# WriteROM_32K_Proto.net
KiCad netlist of a schematic drawn in EAGLE
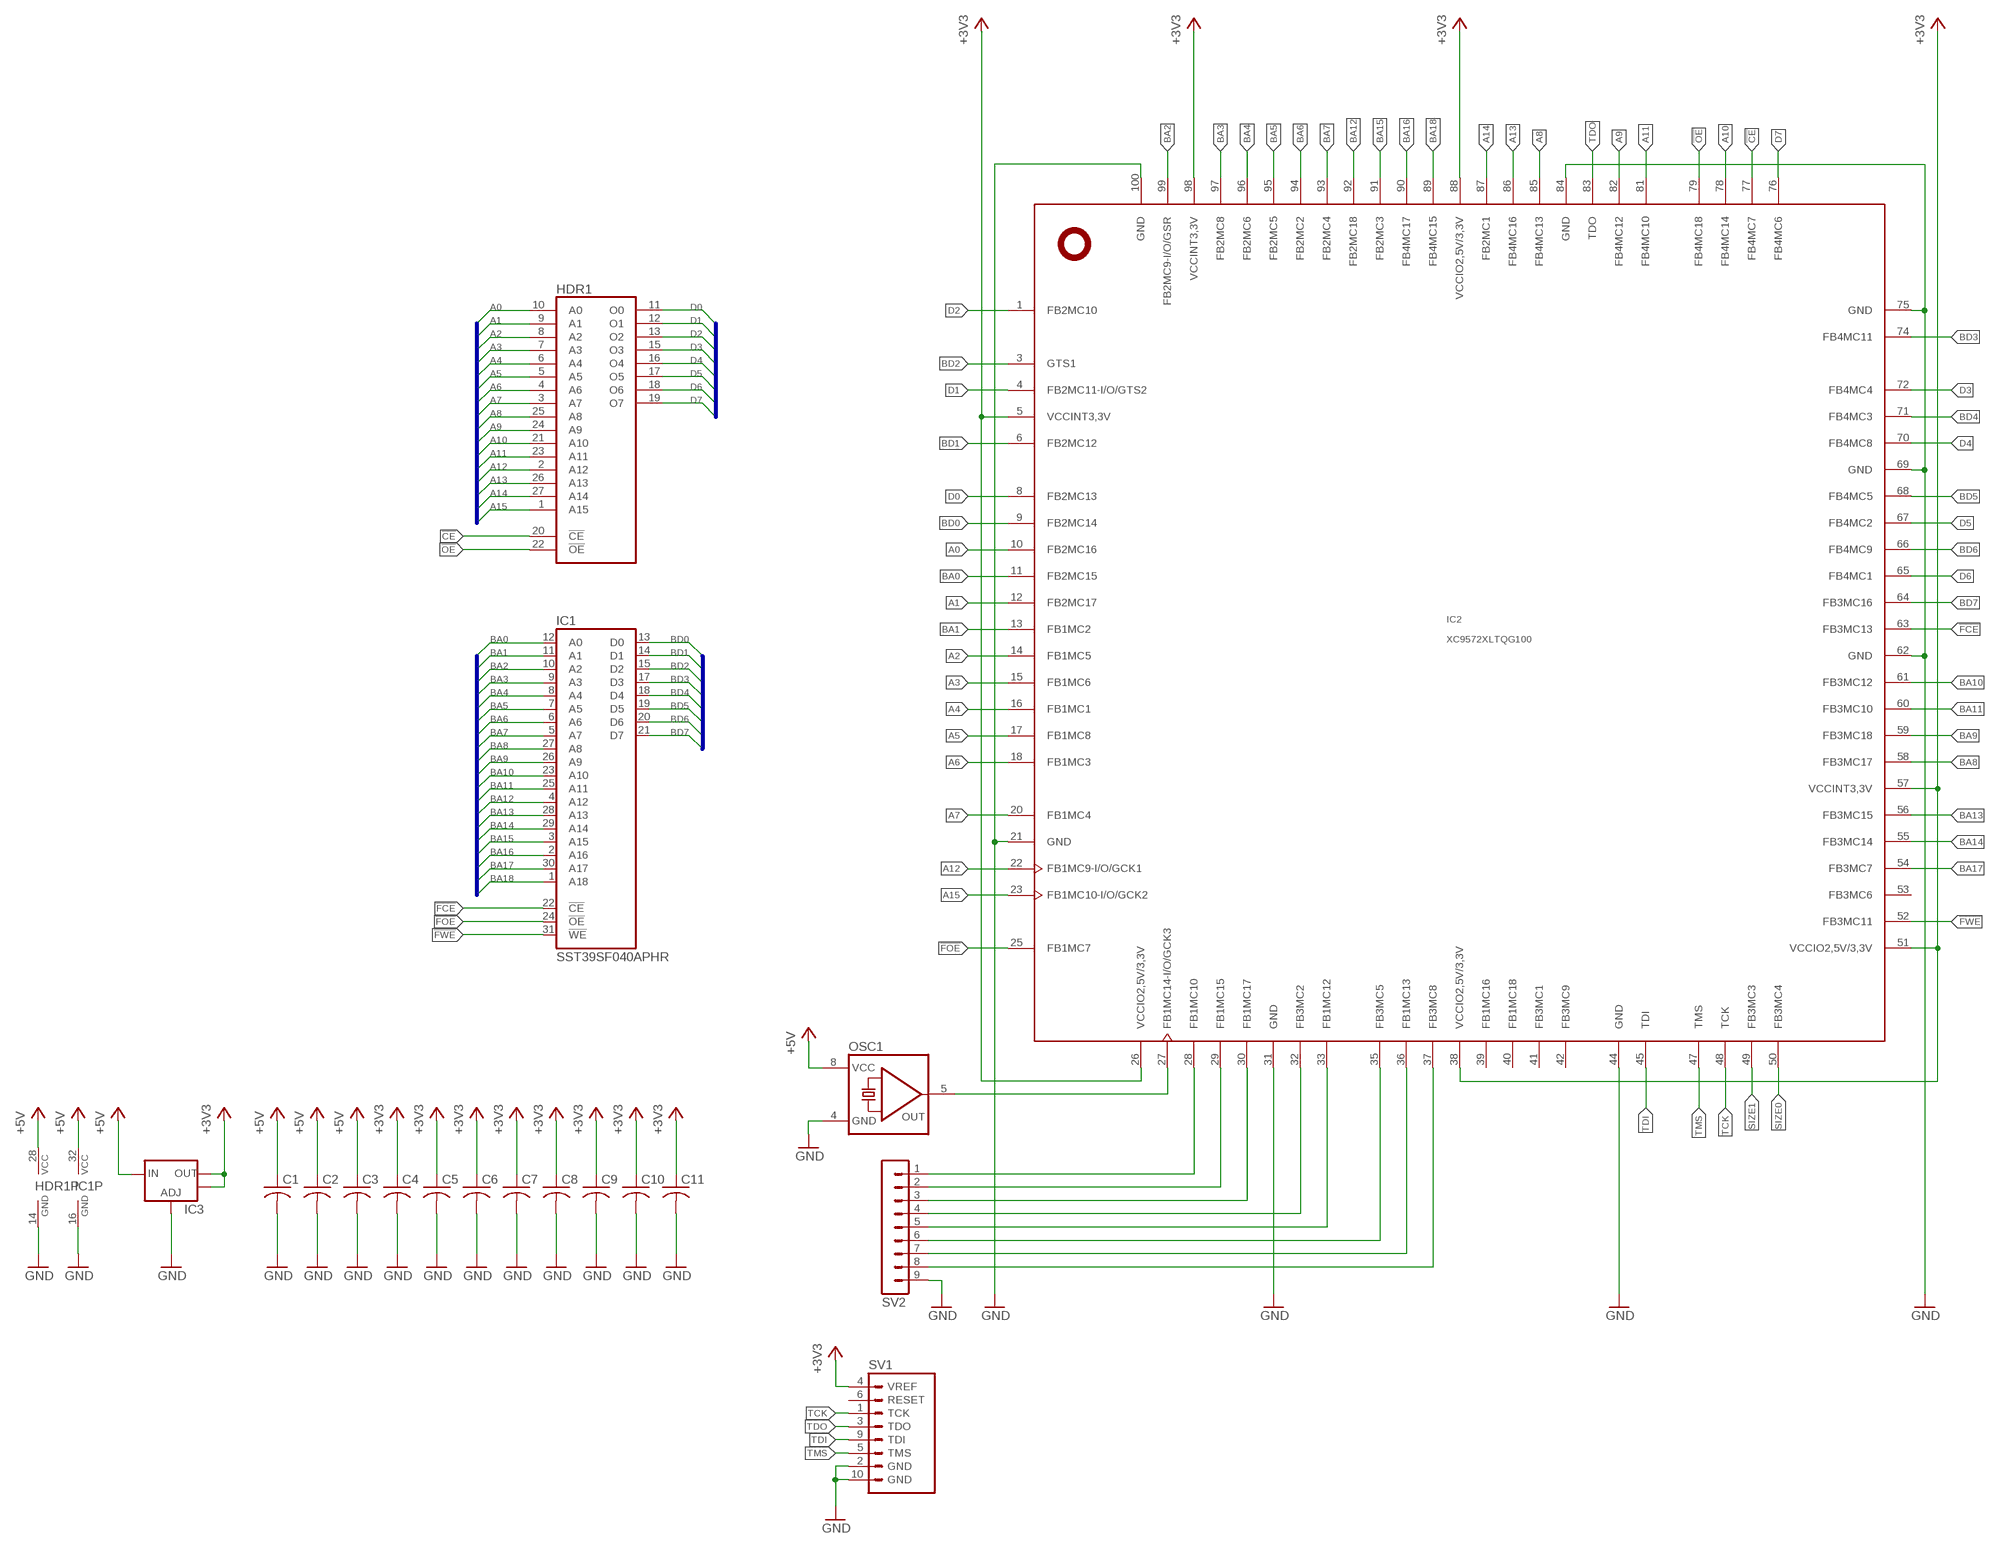
[diagram p0: schematic, sheet 1]

(export (version "E")
  (design (tool "Eeschema 10.0.6"))
  (components
    (comp (ref "C1")
      (value "C-USC0805")
      (footprint "eagle-import:C0805")
      (libsource (lib "eagle-import") (part "C-USC0805"))
    )
    (comp (ref "C2")
      (value "C-USC0402")
      (footprint "eagle-import:C0402")
      (libsource (lib "eagle-import") (part "C-USC0402"))
    )
    (comp (ref "C3")
      (value "C-USC0402")
      (footprint "eagle-import:C0402")
      (libsource (lib "eagle-import") (part "C-USC0402"))
    )
    (comp (ref "C4")
      (value "C-USC0805")
      (footprint "eagle-import:C0805")
      (libsource (lib "eagle-import") (part "C-USC0805"))
    )
    (comp (ref "C5")
      (value "C-USC0402")
      (footprint "eagle-import:C0402")
      (libsource (lib "eagle-import") (part "C-USC0402"))
    )
    (comp (ref "C6")
      (value "C-USC0402")
      (footprint "eagle-import:C0402")
      (libsource (lib "eagle-import") (part "C-USC0402"))
    )
    (comp (ref "C7")
      (value "C-USC0402")
      (footprint "eagle-import:C0402")
      (libsource (lib "eagle-import") (part "C-USC0402"))
    )
    (comp (ref "C8")
      (value "C-USC0402")
      (footprint "eagle-import:C0402")
      (libsource (lib "eagle-import") (part "C-USC0402"))
    )
    (comp (ref "C9")
      (value "C-USC0402")
      (footprint "eagle-import:C0402")
      (libsource (lib "eagle-import") (part "C-USC0402"))
    )
    (comp (ref "C10")
      (value "C-USC0402")
      (footprint "eagle-import:C0402")
      (libsource (lib "eagle-import") (part "C-USC0402"))
    )
    (comp (ref "C11")
      (value "C-USC0402")
      (footprint "eagle-import:C0402")
      (libsource (lib "eagle-import") (part "C-USC0402"))
    )
    (comp (ref "HDR1")
      (value "27512")
      (footprint "eagle-import:DIL28")
      (libsource (lib "eagle-import") (part "27512"))
    )
    (comp (ref "IC1")
      (value "SST39SF040APHR")
      (footprint "eagle-import:DIL32-RP")
      (libsource (lib "eagle-import") (part "SST39SF040APHR"))
    )
    (comp (ref "IC2")
      (value "XC9572XLTQG100")
      (footprint "eagle-import:TQFP100")
      (libsource (lib "eagle-import") (part "XC9572XLTQG100"))
    )
    (comp (ref "IC3")
      (value "V_REG_LM1117SOT223")
      (footprint "eagle-import:SOT223")
      (libsource (lib "eagle-import") (part "V_REG_LM1117SOT223"))
    )
    (comp (ref "OSC1")
      (value "QG5460")
      (footprint "eagle-import:DIL08S")
      (libsource (lib "eagle-import") (part "QG5460"))
    )
    (comp (ref "SV1")
      (value "JTAG")
      (footprint "eagle-import:JTAG")
      (libsource (lib "eagle-import") (part "JTAG"))
    )
    (comp (ref "SV2")
      (value "MA09-1")
      (footprint "eagle-import:MA09-1")
      (libsource (lib "eagle-import") (part "MA09-1"))
    )
  )
  (nets
    (net (code "1") (name "+3V3") (class "Default")
      (node (ref "C10") (pin "1") (pinfunction "1_1") (pintype "passive"))
      (node (ref "C11") (pin "1") (pinfunction "1_1") (pintype "passive"))
      (node (ref "C4") (pin "1") (pinfunction "1_1") (pintype "passive"))
      (node (ref "C5") (pin "1") (pinfunction "1_1") (pintype "passive"))
      (node (ref "C6") (pin "1") (pinfunction "1_1") (pintype "passive"))
      (node (ref "C7") (pin "1") (pinfunction "1_1") (pintype "passive"))
      (node (ref "C8") (pin "1") (pinfunction "1_1") (pintype "passive"))
      (node (ref "C9") (pin "1") (pinfunction "1_1") (pintype "passive"))
      (node (ref "IC2") (pin "26") (pinfunction "VCCIO2,5V/3,3V_26") (pintype "power_in"))
      (node (ref "IC2") (pin "38") (pinfunction "VCCIO2,5V/3,3V_38") (pintype "power_in"))
      (node (ref "IC2") (pin "5") (pinfunction "VCCINT3,3V_5") (pintype "power_in"))
      (node (ref "IC2") (pin "51") (pinfunction "VCCIO2,5V/3,3V_51") (pintype "power_in"))
      (node (ref "IC2") (pin "57") (pinfunction "VCCINT3,3V_57") (pintype "power_in"))
      (node (ref "IC2") (pin "88") (pinfunction "VCCIO2,5V/3,3V_88") (pintype "power_in"))
      (node (ref "IC2") (pin "98") (pinfunction "VCCINT3,3V_98") (pintype "power_in"))
      (node (ref "IC3") (pin "2") (pinfunction "OUT_2") (pintype "output"))
      (node (ref "IC3") (pin "4") (pinfunction "OUT_4") (pintype "output"))
      (node (ref "SV1") (pin "4") (pinfunction "VREF_4") (pintype "power_in"))
    )
    (net (code "2") (name "+5V") (class "Default")
      (node (ref "C1") (pin "1") (pinfunction "1_1") (pintype "passive"))
      (node (ref "C2") (pin "1") (pinfunction "1_1") (pintype "passive"))
      (node (ref "C3") (pin "1") (pinfunction "1_1") (pintype "passive"))
      (node (ref "HDR1") (pin "28") (pinfunction "VCC_28") (pintype "power_in"))
      (node (ref "IC1") (pin "32") (pinfunction "VCC_32") (pintype "power_in"))
      (node (ref "IC3") (pin "3") (pinfunction "IN_3") (pintype "input"))
      (node (ref "OSC1") (pin "8") (pinfunction "VCC_8") (pintype "power_in"))
    )
    (net (code "3") (name "/~{CE}") (class "Default")
      (node (ref "HDR1") (pin "20") (pinfunction "~{CE}_20") (pintype "input"))
      (node (ref "IC2") (pin "77") (pinfunction "FB4MC7_77") (pintype "bidirectional"))
    )
    (net (code "4") (name "/~{FCE}") (class "Default")
      (node (ref "IC1") (pin "22") (pinfunction "~{CE}_22") (pintype "input"))
      (node (ref "IC2") (pin "63") (pinfunction "FB3MC13_63") (pintype "bidirectional"))
    )
    (net (code "5") (name "/~{FOE}") (class "Default")
      (node (ref "IC1") (pin "24") (pinfunction "~{OE}_24") (pintype "input"))
      (node (ref "IC2") (pin "25") (pinfunction "FB1MC7_25") (pintype "bidirectional"))
    )
    (net (code "6") (name "/~{FWE}") (class "Default")
      (node (ref "IC1") (pin "31") (pinfunction "~{WE}_31") (pintype "input"))
      (node (ref "IC2") (pin "52") (pinfunction "FB3MC11_52") (pintype "bidirectional"))
    )
    (net (code "7") (name "/~{OE}") (class "Default")
      (node (ref "HDR1") (pin "22") (pinfunction "~{OE}_22") (pintype "input"))
      (node (ref "IC2") (pin "79") (pinfunction "FB4MC18_79") (pintype "bidirectional"))
    )
    (net (code "8") (name "A0") (class "Default")
      (node (ref "HDR1") (pin "10") (pinfunction "A0_10") (pintype "input"))
      (node (ref "IC2") (pin "10") (pinfunction "FB2MC16_10") (pintype "bidirectional"))
    )
    (net (code "9") (name "A1") (class "Default")
      (node (ref "HDR1") (pin "9") (pinfunction "A1_9") (pintype "input"))
      (node (ref "IC2") (pin "12") (pinfunction "FB2MC17_12") (pintype "bidirectional"))
    )
    (net (code "10") (name "A2") (class "Default")
      (node (ref "HDR1") (pin "8") (pinfunction "A2_8") (pintype "input"))
      (node (ref "IC2") (pin "14") (pinfunction "FB1MC5_14") (pintype "bidirectional"))
    )
    (net (code "11") (name "A3") (class "Default")
      (node (ref "HDR1") (pin "7") (pinfunction "A3_7") (pintype "input"))
      (node (ref "IC2") (pin "15") (pinfunction "FB1MC6_15") (pintype "bidirectional"))
    )
    (net (code "12") (name "A4") (class "Default")
      (node (ref "HDR1") (pin "6") (pinfunction "A4_6") (pintype "input"))
      (node (ref "IC2") (pin "16") (pinfunction "FB1MC1_16") (pintype "bidirectional"))
    )
    (net (code "13") (name "A5") (class "Default")
      (node (ref "HDR1") (pin "5") (pinfunction "A5_5") (pintype "input"))
      (node (ref "IC2") (pin "17") (pinfunction "FB1MC8_17") (pintype "bidirectional"))
    )
    (net (code "14") (name "A6") (class "Default")
      (node (ref "HDR1") (pin "4") (pinfunction "A6_4") (pintype "input"))
      (node (ref "IC2") (pin "18") (pinfunction "FB1MC3_18") (pintype "bidirectional"))
    )
    (net (code "15") (name "A7") (class "Default")
      (node (ref "HDR1") (pin "3") (pinfunction "A7_3") (pintype "input"))
      (node (ref "IC2") (pin "20") (pinfunction "FB1MC4_20") (pintype "bidirectional"))
    )
    (net (code "16") (name "A8") (class "Default")
      (node (ref "HDR1") (pin "25") (pinfunction "A8_25") (pintype "input"))
      (node (ref "IC2") (pin "85") (pinfunction "FB4MC13_85") (pintype "bidirectional"))
    )
    (net (code "17") (name "A9") (class "Default")
      (node (ref "HDR1") (pin "24") (pinfunction "A9_24") (pintype "input"))
      (node (ref "IC2") (pin "82") (pinfunction "FB4MC12_82") (pintype "bidirectional"))
    )
    (net (code "18") (name "A10") (class "Default")
      (node (ref "HDR1") (pin "21") (pinfunction "A10_21") (pintype "input"))
      (node (ref "IC2") (pin "78") (pinfunction "FB4MC14_78") (pintype "bidirectional"))
    )
    (net (code "19") (name "A11") (class "Default")
      (node (ref "HDR1") (pin "23") (pinfunction "A11_23") (pintype "input"))
      (node (ref "IC2") (pin "81") (pinfunction "FB4MC10_81") (pintype "bidirectional"))
    )
    (net (code "20") (name "A12") (class "Default")
      (node (ref "HDR1") (pin "2") (pinfunction "A12_2") (pintype "input"))
      (node (ref "IC2") (pin "22") (pinfunction "FB1MC9-I/O/GCK1_22") (pintype "bidirectional"))
    )
    (net (code "21") (name "A13") (class "Default")
      (node (ref "HDR1") (pin "26") (pinfunction "A13_26") (pintype "input"))
      (node (ref "IC2") (pin "86") (pinfunction "FB4MC16_86") (pintype "bidirectional"))
    )
    (net (code "22") (name "A14") (class "Default")
      (node (ref "HDR1") (pin "27") (pinfunction "A14_27") (pintype "input"))
      (node (ref "IC2") (pin "87") (pinfunction "FB2MC1_87") (pintype "bidirectional"))
    )
    (net (code "23") (name "A15") (class "Default")
      (node (ref "HDR1") (pin "1") (pinfunction "A15_1") (pintype "input"))
      (node (ref "IC2") (pin "23") (pinfunction "FB1MC10-I/O/GCK2_23") (pintype "bidirectional"))
    )
    (net (code "24") (name "BA0") (class "Default")
      (node (ref "IC1") (pin "12") (pinfunction "A0_12") (pintype "input"))
      (node (ref "IC2") (pin "11") (pinfunction "FB2MC15_11") (pintype "bidirectional"))
    )
    (net (code "25") (name "BA1") (class "Default")
      (node (ref "IC1") (pin "11") (pinfunction "A1_11") (pintype "input"))
      (node (ref "IC2") (pin "13") (pinfunction "FB1MC2_13") (pintype "bidirectional"))
    )
    (net (code "26") (name "BA2") (class "Default")
      (node (ref "IC1") (pin "10") (pinfunction "A2_10") (pintype "input"))
      (node (ref "IC2") (pin "99") (pinfunction "FB2MC9-I/O/GSR_99") (pintype "bidirectional"))
    )
    (net (code "27") (name "BA3") (class "Default")
      (node (ref "IC1") (pin "9") (pinfunction "A3_9") (pintype "input"))
      (node (ref "IC2") (pin "97") (pinfunction "FB2MC8_97") (pintype "bidirectional"))
    )
    (net (code "28") (name "BA4") (class "Default")
      (node (ref "IC1") (pin "8") (pinfunction "A4_8") (pintype "input"))
      (node (ref "IC2") (pin "96") (pinfunction "FB2MC6_96") (pintype "bidirectional"))
    )
    (net (code "29") (name "BA5") (class "Default")
      (node (ref "IC1") (pin "7") (pinfunction "A5_7") (pintype "input"))
      (node (ref "IC2") (pin "95") (pinfunction "FB2MC5_95") (pintype "bidirectional"))
    )
    (net (code "30") (name "BA6") (class "Default")
      (node (ref "IC1") (pin "6") (pinfunction "A6_6") (pintype "input"))
      (node (ref "IC2") (pin "94") (pinfunction "FB2MC2_94") (pintype "bidirectional"))
    )
    (net (code "31") (name "BA7") (class "Default")
      (node (ref "IC1") (pin "5") (pinfunction "A7_5") (pintype "input"))
      (node (ref "IC2") (pin "93") (pinfunction "FB2MC4_93") (pintype "bidirectional"))
    )
    (net (code "32") (name "BA8") (class "Default")
      (node (ref "IC1") (pin "27") (pinfunction "A8_27") (pintype "input"))
      (node (ref "IC2") (pin "58") (pinfunction "FB3MC17_58") (pintype "bidirectional"))
    )
    (net (code "33") (name "BA9") (class "Default")
      (node (ref "IC1") (pin "26") (pinfunction "A9_26") (pintype "input"))
      (node (ref "IC2") (pin "59") (pinfunction "FB3MC18_59") (pintype "bidirectional"))
    )
    (net (code "34") (name "BA10") (class "Default")
      (node (ref "IC1") (pin "23") (pinfunction "A10_23") (pintype "input"))
      (node (ref "IC2") (pin "61") (pinfunction "FB3MC12_61") (pintype "bidirectional"))
    )
    (net (code "35") (name "BA11") (class "Default")
      (node (ref "IC1") (pin "25") (pinfunction "A11_25") (pintype "input"))
      (node (ref "IC2") (pin "60") (pinfunction "FB3MC10_60") (pintype "bidirectional"))
    )
    (net (code "36") (name "BA12") (class "Default")
      (node (ref "IC1") (pin "4") (pinfunction "A12_4") (pintype "input"))
      (node (ref "IC2") (pin "92") (pinfunction "FB2MC18_92") (pintype "bidirectional"))
    )
    (net (code "37") (name "BA13") (class "Default")
      (node (ref "IC1") (pin "28") (pinfunction "A13_28") (pintype "input"))
      (node (ref "IC2") (pin "56") (pinfunction "FB3MC15_56") (pintype "bidirectional"))
    )
    (net (code "38") (name "BA14") (class "Default")
      (node (ref "IC1") (pin "29") (pinfunction "A14_29") (pintype "input"))
      (node (ref "IC2") (pin "55") (pinfunction "FB3MC14_55") (pintype "bidirectional"))
    )
    (net (code "39") (name "BA15") (class "Default")
      (node (ref "IC1") (pin "3") (pinfunction "A15_3") (pintype "input"))
      (node (ref "IC2") (pin "91") (pinfunction "FB2MC3_91") (pintype "bidirectional"))
    )
    (net (code "40") (name "BA16") (class "Default")
      (node (ref "IC1") (pin "2") (pinfunction "A16_2") (pintype "input"))
      (node (ref "IC2") (pin "90") (pinfunction "FB4MC17_90") (pintype "bidirectional"))
    )
    (net (code "41") (name "BA17") (class "Default")
      (node (ref "IC1") (pin "30") (pinfunction "A17_30") (pintype "input"))
      (node (ref "IC2") (pin "54") (pinfunction "FB3MC7_54") (pintype "bidirectional"))
    )
    (net (code "42") (name "BA18") (class "Default")
      (node (ref "IC1") (pin "1") (pinfunction "A18_1") (pintype "input"))
      (node (ref "IC2") (pin "89") (pinfunction "FB4MC15_89") (pintype "bidirectional"))
    )
    (net (code "43") (name "BD0") (class "Default")
      (node (ref "IC1") (pin "13") (pinfunction "D0_13") (pintype "bidirectional"))
      (node (ref "IC2") (pin "9") (pinfunction "FB2MC14_9") (pintype "bidirectional"))
    )
    (net (code "44") (name "BD1") (class "Default")
      (node (ref "IC1") (pin "14") (pinfunction "D1_14") (pintype "bidirectional"))
      (node (ref "IC2") (pin "6") (pinfunction "FB2MC12_6") (pintype "bidirectional"))
    )
    (net (code "45") (name "BD2") (class "Default")
      (node (ref "IC1") (pin "15") (pinfunction "D2_15") (pintype "bidirectional"))
      (node (ref "IC2") (pin "3") (pinfunction "GTS1_3") (pintype "bidirectional"))
    )
    (net (code "46") (name "BD3") (class "Default")
      (node (ref "IC1") (pin "17") (pinfunction "D3_17") (pintype "bidirectional"))
      (node (ref "IC2") (pin "74") (pinfunction "FB4MC11_74") (pintype "bidirectional"))
    )
    (net (code "47") (name "BD4") (class "Default")
      (node (ref "IC1") (pin "18") (pinfunction "D4_18") (pintype "bidirectional"))
      (node (ref "IC2") (pin "71") (pinfunction "FB4MC3_71") (pintype "bidirectional"))
    )
    (net (code "48") (name "BD5") (class "Default")
      (node (ref "IC1") (pin "19") (pinfunction "D5_19") (pintype "bidirectional"))
      (node (ref "IC2") (pin "68") (pinfunction "FB4MC5_68") (pintype "bidirectional"))
    )
    (net (code "49") (name "BD6") (class "Default")
      (node (ref "IC1") (pin "20") (pinfunction "D6_20") (pintype "bidirectional"))
      (node (ref "IC2") (pin "66") (pinfunction "FB4MC9_66") (pintype "bidirectional"))
    )
    (net (code "50") (name "BD7") (class "Default")
      (node (ref "IC1") (pin "21") (pinfunction "D7_21") (pintype "bidirectional"))
      (node (ref "IC2") (pin "64") (pinfunction "FB3MC16_64") (pintype "bidirectional"))
    )
    (net (code "51") (name "D0") (class "Default")
      (node (ref "HDR1") (pin "11") (pinfunction "O0_11") (pintype "tri_state"))
      (node (ref "IC2") (pin "8") (pinfunction "FB2MC13_8") (pintype "bidirectional"))
    )
    (net (code "52") (name "D1") (class "Default")
      (node (ref "HDR1") (pin "12") (pinfunction "O1_12") (pintype "tri_state"))
      (node (ref "IC2") (pin "4") (pinfunction "FB2MC11-I/O/GTS2_4") (pintype "bidirectional"))
    )
    (net (code "53") (name "D2") (class "Default")
      (node (ref "HDR1") (pin "13") (pinfunction "O2_13") (pintype "tri_state"))
      (node (ref "IC2") (pin "1") (pinfunction "FB2MC10_1") (pintype "bidirectional"))
    )
    (net (code "54") (name "D3") (class "Default")
      (node (ref "HDR1") (pin "15") (pinfunction "O3_15") (pintype "tri_state"))
      (node (ref "IC2") (pin "72") (pinfunction "FB4MC4_72") (pintype "bidirectional"))
    )
    (net (code "55") (name "D4") (class "Default")
      (node (ref "HDR1") (pin "16") (pinfunction "O4_16") (pintype "tri_state"))
      (node (ref "IC2") (pin "70") (pinfunction "FB4MC8_70") (pintype "bidirectional"))
    )
    (net (code "56") (name "D5") (class "Default")
      (node (ref "HDR1") (pin "17") (pinfunction "O5_17") (pintype "tri_state"))
      (node (ref "IC2") (pin "67") (pinfunction "FB4MC2_67") (pintype "bidirectional"))
    )
    (net (code "57") (name "D6") (class "Default")
      (node (ref "HDR1") (pin "18") (pinfunction "O6_18") (pintype "tri_state"))
      (node (ref "IC2") (pin "65") (pinfunction "FB4MC1_65") (pintype "bidirectional"))
    )
    (net (code "58") (name "D7") (class "Default")
      (node (ref "HDR1") (pin "19") (pinfunction "O7_19") (pintype "tri_state"))
      (node (ref "IC2") (pin "76") (pinfunction "FB4MC6_76") (pintype "bidirectional"))
    )
    (net (code "59") (name "GND") (class "Default")
      (node (ref "C1") (pin "2") (pinfunction "2_2") (pintype "passive"))
      (node (ref "C10") (pin "2") (pinfunction "2_2") (pintype "passive"))
      (node (ref "C11") (pin "2") (pinfunction "2_2") (pintype "passive"))
      (node (ref "C2") (pin "2") (pinfunction "2_2") (pintype "passive"))
      (node (ref "C3") (pin "2") (pinfunction "2_2") (pintype "passive"))
      (node (ref "C4") (pin "2") (pinfunction "2_2") (pintype "passive"))
      (node (ref "C5") (pin "2") (pinfunction "2_2") (pintype "passive"))
      (node (ref "C6") (pin "2") (pinfunction "2_2") (pintype "passive"))
      (node (ref "C7") (pin "2") (pinfunction "2_2") (pintype "passive"))
      (node (ref "C8") (pin "2") (pinfunction "2_2") (pintype "passive"))
      (node (ref "C9") (pin "2") (pinfunction "2_2") (pintype "passive"))
      (node (ref "HDR1") (pin "14") (pinfunction "GND_14") (pintype "power_in"))
      (node (ref "IC1") (pin "16") (pinfunction "GND_16") (pintype "power_in"))
      (node (ref "IC2") (pin "100") (pinfunction "GND_100") (pintype "power_in"))
      (node (ref "IC2") (pin "21") (pinfunction "GND_21") (pintype "power_in"))
      (node (ref "IC2") (pin "31") (pinfunction "GND_31") (pintype "power_in"))
      (node (ref "IC2") (pin "44") (pinfunction "GND_44") (pintype "power_in"))
      (node (ref "IC2") (pin "62") (pinfunction "GND_62") (pintype "power_in"))
      (node (ref "IC2") (pin "69") (pinfunction "GND_69") (pintype "power_in"))
      (node (ref "IC2") (pin "75") (pinfunction "GND_75") (pintype "power_in"))
      (node (ref "IC2") (pin "84") (pinfunction "GND_84") (pintype "power_in"))
      (node (ref "IC3") (pin "1") (pinfunction "ADJ_1") (pintype "input"))
      (node (ref "OSC1") (pin "4") (pinfunction "GND_4") (pintype "power_in"))
      (node (ref "SV1") (pin "10") (pinfunction "GND_10") (pintype "power_in"))
      (node (ref "SV1") (pin "2") (pinfunction "GND_2") (pintype "power_in"))
      (node (ref "SV2") (pin "9") (pinfunction "9_9") (pintype "passive"))
    )
    (net (code "60") (name "Net-(IC2-FB1MC10)") (class "Default")
      (node (ref "IC2") (pin "28") (pinfunction "FB1MC10_28") (pintype "bidirectional"))
      (node (ref "SV2") (pin "1") (pinfunction "1_1") (pintype "passive"))
    )
    (net (code "61") (name "Net-(IC2-FB1MC12)") (class "Default")
      (node (ref "IC2") (pin "33") (pinfunction "FB1MC12_33") (pintype "bidirectional"))
      (node (ref "SV2") (pin "5") (pinfunction "5_5") (pintype "passive"))
    )
    (net (code "62") (name "Net-(IC2-FB1MC13)") (class "Default")
      (node (ref "IC2") (pin "36") (pinfunction "FB1MC13_36") (pintype "bidirectional"))
      (node (ref "SV2") (pin "7") (pinfunction "7_7") (pintype "passive"))
    )
    (net (code "63") (name "Net-(IC2-FB1MC14-I{slash}O{slash}GCK3)") (class "Default")
      (node (ref "IC2") (pin "27") (pinfunction "FB1MC14-I/O/GCK3_27") (pintype "bidirectional"))
      (node (ref "OSC1") (pin "5") (pinfunction "OUT_5") (pintype "output"))
    )
    (net (code "64") (name "Net-(IC2-FB1MC15)") (class "Default")
      (node (ref "IC2") (pin "29") (pinfunction "FB1MC15_29") (pintype "bidirectional"))
      (node (ref "SV2") (pin "2") (pinfunction "2_2") (pintype "passive"))
    )
    (net (code "65") (name "Net-(IC2-FB1MC17)") (class "Default")
      (node (ref "IC2") (pin "30") (pinfunction "FB1MC17_30") (pintype "bidirectional"))
      (node (ref "SV2") (pin "3") (pinfunction "3_3") (pintype "passive"))
    )
    (net (code "66") (name "Net-(IC2-FB3MC2)") (class "Default")
      (node (ref "IC2") (pin "32") (pinfunction "FB3MC2_32") (pintype "bidirectional"))
      (node (ref "SV2") (pin "4") (pinfunction "4_4") (pintype "passive"))
    )
    (net (code "67") (name "Net-(IC2-FB3MC5)") (class "Default")
      (node (ref "IC2") (pin "35") (pinfunction "FB3MC5_35") (pintype "bidirectional"))
      (node (ref "SV2") (pin "6") (pinfunction "6_6") (pintype "passive"))
    )
    (net (code "68") (name "Net-(IC2-FB3MC8)") (class "Default")
      (node (ref "IC2") (pin "37") (pinfunction "FB3MC8_37") (pintype "bidirectional"))
      (node (ref "SV2") (pin "8") (pinfunction "8_8") (pintype "passive"))
    )
    (net (code "69") (name "SIZE0") (class "Default")
      (node (ref "IC2") (pin "50") (pinfunction "FB3MC4_50") (pintype "bidirectional"))
    )
    (net (code "70") (name "SIZE1") (class "Default")
      (node (ref "IC2") (pin "49") (pinfunction "FB3MC3_49") (pintype "bidirectional"))
    )
    (net (code "71") (name "TCK") (class "Default")
      (node (ref "IC2") (pin "48") (pinfunction "TCK_48") (pintype "bidirectional"))
      (node (ref "SV1") (pin "1") (pinfunction "TCK_1") (pintype "output"))
    )
    (net (code "72") (name "TDI") (class "Default")
      (node (ref "IC2") (pin "45") (pinfunction "TDI_45") (pintype "bidirectional"))
      (node (ref "SV1") (pin "9") (pinfunction "TDI_9") (pintype "input"))
    )
    (net (code "73") (name "TDO") (class "Default")
      (node (ref "IC2") (pin "83") (pinfunction "TDO_83") (pintype "bidirectional"))
      (node (ref "SV1") (pin "3") (pinfunction "TDO_3") (pintype "output"))
    )
    (net (code "74") (name "TMS") (class "Default")
      (node (ref "IC2") (pin "47") (pinfunction "TMS_47") (pintype "bidirectional"))
      (node (ref "SV1") (pin "5") (pinfunction "TMS_5") (pintype "output"))
    )
    (net (code "75") (name "unconnected-(IC2-FB1MC16-Pad39)") (class "Default")
      (node (ref "IC2") (pin "39") (pinfunction "FB1MC16_39") (pintype "bidirectional"))
    )
    (net (code "76") (name "unconnected-(IC2-FB1MC18-Pad40)") (class "Default")
      (node (ref "IC2") (pin "40") (pinfunction "FB1MC18_40") (pintype "bidirectional"))
    )
    (net (code "77") (name "unconnected-(IC2-FB3MC1-Pad41)") (class "Default")
      (node (ref "IC2") (pin "41") (pinfunction "FB3MC1_41") (pintype "bidirectional"))
    )
    (net (code "78") (name "unconnected-(IC2-FB3MC6-Pad53)") (class "Default")
      (node (ref "IC2") (pin "53") (pinfunction "FB3MC6_53") (pintype "bidirectional"))
    )
    (net (code "79") (name "unconnected-(IC2-FB3MC9-Pad42)") (class "Default")
      (node (ref "IC2") (pin "42") (pinfunction "FB3MC9_42") (pintype "bidirectional"))
    )
    (net (code "80") (name "unconnected-(SV1-RESET-Pad6)") (class "Default")
      (node (ref "SV1") (pin "6") (pinfunction "RESET_6") (pintype "output"))
    )
  )
)
